# HoloCubicConnect_211230.net
KiCad netlist of a schematic drawn in Altium Designer
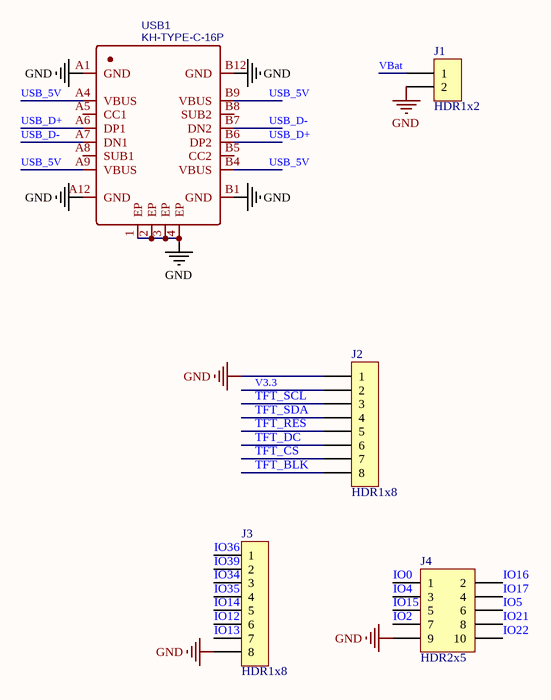
[diagram p0: HoloCubicConnect_211230.SchDoc]

(export (version "E")
  (design (tool "Eeschema 10.0.6"))
  (components
    (comp (ref "J1")
      (value "HDR1x2")
      (footprint "PIN-2-2.54-1.0")
      (description "Connector")
      (libsource (lib "General") (part "HDR1x2"))
    )
    (comp (ref "J2")
      (value "HDR1x8")
      (footprint "PIN-8-2.54-1.0")
      (description "Connector")
      (libsource (lib "General") (part "HDR1x8"))
    )
    (comp (ref "J3")
      (value "HDR1x8")
      (footprint "PIN-8-2.54-1.0")
      (description "Connector")
      (libsource (lib "General") (part "HDR1x8"))
    )
    (comp (ref "J4")
      (value "HDR2x5")
      (footprint "PIN-2x5-2.54-1.0")
      (description "Connector")
      (libsource (lib "General") (part "HDR2x5"))
    )
    (comp (ref "USB1")
      (value "KH-TYPE-C-16P")
      (footprint "USB-C-SMD_KH-TYPE-C-16P")
      (fields (field (name "BOM_SUPPLIER PART") "C709357") (field (name "CONTRIBUTOR") "LCSC"))
      (libsource (lib "altium-import") (part "root_0_KH-TYPE-C-16P_"))
    )
  )
  (nets
    (net (code "1") (name "/IO0") (class "Default")
      (node (ref "J4") (pin "1") (pinfunction "1_1") (pintype "passive"))
    )
    (net (code "2") (name "/IO2") (class "Default")
      (node (ref "J4") (pin "7") (pinfunction "7_7") (pintype "passive"))
    )
    (net (code "3") (name "/IO4") (class "Default")
      (node (ref "J4") (pin "3") (pinfunction "3_3") (pintype "passive"))
    )
    (net (code "4") (name "/IO5") (class "Default")
      (node (ref "J4") (pin "6") (pinfunction "6_6") (pintype "passive"))
    )
    (net (code "5") (name "/IO12") (class "Default")
      (node (ref "J3") (pin "6") (pinfunction "6_6") (pintype "passive"))
    )
    (net (code "6") (name "/IO13") (class "Default")
      (node (ref "J3") (pin "7") (pinfunction "7_7") (pintype "passive"))
    )
    (net (code "7") (name "/IO14") (class "Default")
      (node (ref "J3") (pin "5") (pinfunction "5_5") (pintype "passive"))
    )
    (net (code "8") (name "/IO15") (class "Default")
      (node (ref "J4") (pin "5") (pinfunction "5_5") (pintype "passive"))
    )
    (net (code "9") (name "/IO16") (class "Default")
      (node (ref "J4") (pin "2") (pinfunction "2_2") (pintype "passive"))
    )
    (net (code "10") (name "/IO17") (class "Default")
      (node (ref "J4") (pin "4") (pinfunction "4_4") (pintype "passive"))
    )
    (net (code "11") (name "/IO21") (class "Default")
      (node (ref "J4") (pin "8") (pinfunction "8_8") (pintype "passive"))
    )
    (net (code "12") (name "/IO22") (class "Default")
      (node (ref "J4") (pin "10") (pinfunction "10_10") (pintype "passive"))
    )
    (net (code "13") (name "/IO34") (class "Default")
      (node (ref "J3") (pin "3") (pinfunction "3_3") (pintype "passive"))
    )
    (net (code "14") (name "/IO35") (class "Default")
      (node (ref "J3") (pin "4") (pinfunction "4_4") (pintype "passive"))
    )
    (net (code "15") (name "/IO36") (class "Default")
      (node (ref "J3") (pin "1") (pinfunction "1_1") (pintype "passive"))
    )
    (net (code "16") (name "/IO39") (class "Default")
      (node (ref "J3") (pin "2") (pinfunction "2_2") (pintype "passive"))
    )
    (net (code "17") (name "/TFT_BLK") (class "Default")
      (node (ref "J2") (pin "8") (pinfunction "8_8") (pintype "passive"))
    )
    (net (code "18") (name "/TFT_CS") (class "Default")
      (node (ref "J2") (pin "7") (pinfunction "7_7") (pintype "passive"))
    )
    (net (code "19") (name "/TFT_DC") (class "Default")
      (node (ref "J2") (pin "6") (pinfunction "6_6") (pintype "passive"))
    )
    (net (code "20") (name "/TFT_RES") (class "Default")
      (node (ref "J2") (pin "5") (pinfunction "5_5") (pintype "passive"))
    )
    (net (code "21") (name "/TFT_SCL") (class "Default")
      (node (ref "J2") (pin "3") (pinfunction "3_3") (pintype "passive"))
    )
    (net (code "22") (name "/TFT_SDA") (class "Default")
      (node (ref "J2") (pin "4") (pinfunction "4_4") (pintype "passive"))
    )
    (net (code "23") (name "/USB_5V") (class "Default")
      (node (ref "USB1") (pin "A4") (pinfunction "VBUS_A4") (pintype "passive"))
      (node (ref "USB1") (pin "A9") (pinfunction "VBUS_A9") (pintype "passive"))
      (node (ref "USB1") (pin "B4") (pinfunction "VBUS_B4") (pintype "passive"))
      (node (ref "USB1") (pin "B9") (pinfunction "VBUS_B9") (pintype "passive"))
    )
    (net (code "24") (name "/USB_D+") (class "Default")
      (node (ref "USB1") (pin "A6") (pinfunction "DP1_A6") (pintype "passive"))
      (node (ref "USB1") (pin "B6") (pinfunction "DP2_B6") (pintype "passive"))
    )
    (net (code "25") (name "/USB_D-") (class "Default")
      (node (ref "USB1") (pin "A7") (pinfunction "DN1_A7") (pintype "passive"))
      (node (ref "USB1") (pin "B7") (pinfunction "DN2_B7") (pintype "passive"))
    )
    (net (code "26") (name "/V3.3") (class "Default")
      (node (ref "J2") (pin "2") (pinfunction "2_2") (pintype "passive"))
    )
    (net (code "27") (name "/VBat") (class "Default")
      (node (ref "J1") (pin "1") (pinfunction "1_1") (pintype "passive"))
    )
    (net (code "28") (name "GND") (class "Default")
      (node (ref "J1") (pin "2") (pinfunction "2_2") (pintype "passive"))
      (node (ref "J2") (pin "1") (pinfunction "1_1") (pintype "passive"))
      (node (ref "J3") (pin "8") (pinfunction "8_8") (pintype "passive"))
      (node (ref "J4") (pin "9") (pinfunction "9_9") (pintype "passive"))
      (node (ref "USB1") (pin "1") (pinfunction "EP_1") (pintype "passive"))
      (node (ref "USB1") (pin "2") (pinfunction "EP_2") (pintype "passive"))
      (node (ref "USB1") (pin "3") (pinfunction "EP_3") (pintype "passive"))
      (node (ref "USB1") (pin "4") (pinfunction "EP_4") (pintype "passive"))
      (node (ref "USB1") (pin "A1") (pinfunction "GND_A1") (pintype "passive"))
      (node (ref "USB1") (pin "A12") (pinfunction "GND_A12") (pintype "passive"))
      (node (ref "USB1") (pin "B1") (pinfunction "GND_B1") (pintype "passive"))
      (node (ref "USB1") (pin "B12") (pinfunction "GND_B12") (pintype "passive"))
    )
    (net (code "29") (name "unconnected-(USB1-CC1-PadA5)") (class "Default")
      (node (ref "USB1") (pin "A5") (pinfunction "CC1_A5") (pintype "passive"))
    )
    (net (code "30") (name "unconnected-(USB1-CC2-PadB5)") (class "Default")
      (node (ref "USB1") (pin "B5") (pinfunction "CC2_B5") (pintype "passive"))
    )
    (net (code "31") (name "unconnected-(USB1-SUB1-PadA8)") (class "Default")
      (node (ref "USB1") (pin "A8") (pinfunction "SUB1_A8") (pintype "passive"))
    )
    (net (code "32") (name "unconnected-(USB1-SUB2-PadB8)") (class "Default")
      (node (ref "USB1") (pin "B8") (pinfunction "SUB2_B8") (pintype "passive"))
    )
  )
)
